# Trepanat_Sensors_3.net
KiCad netlist of a schematic drawn in Altium Designer
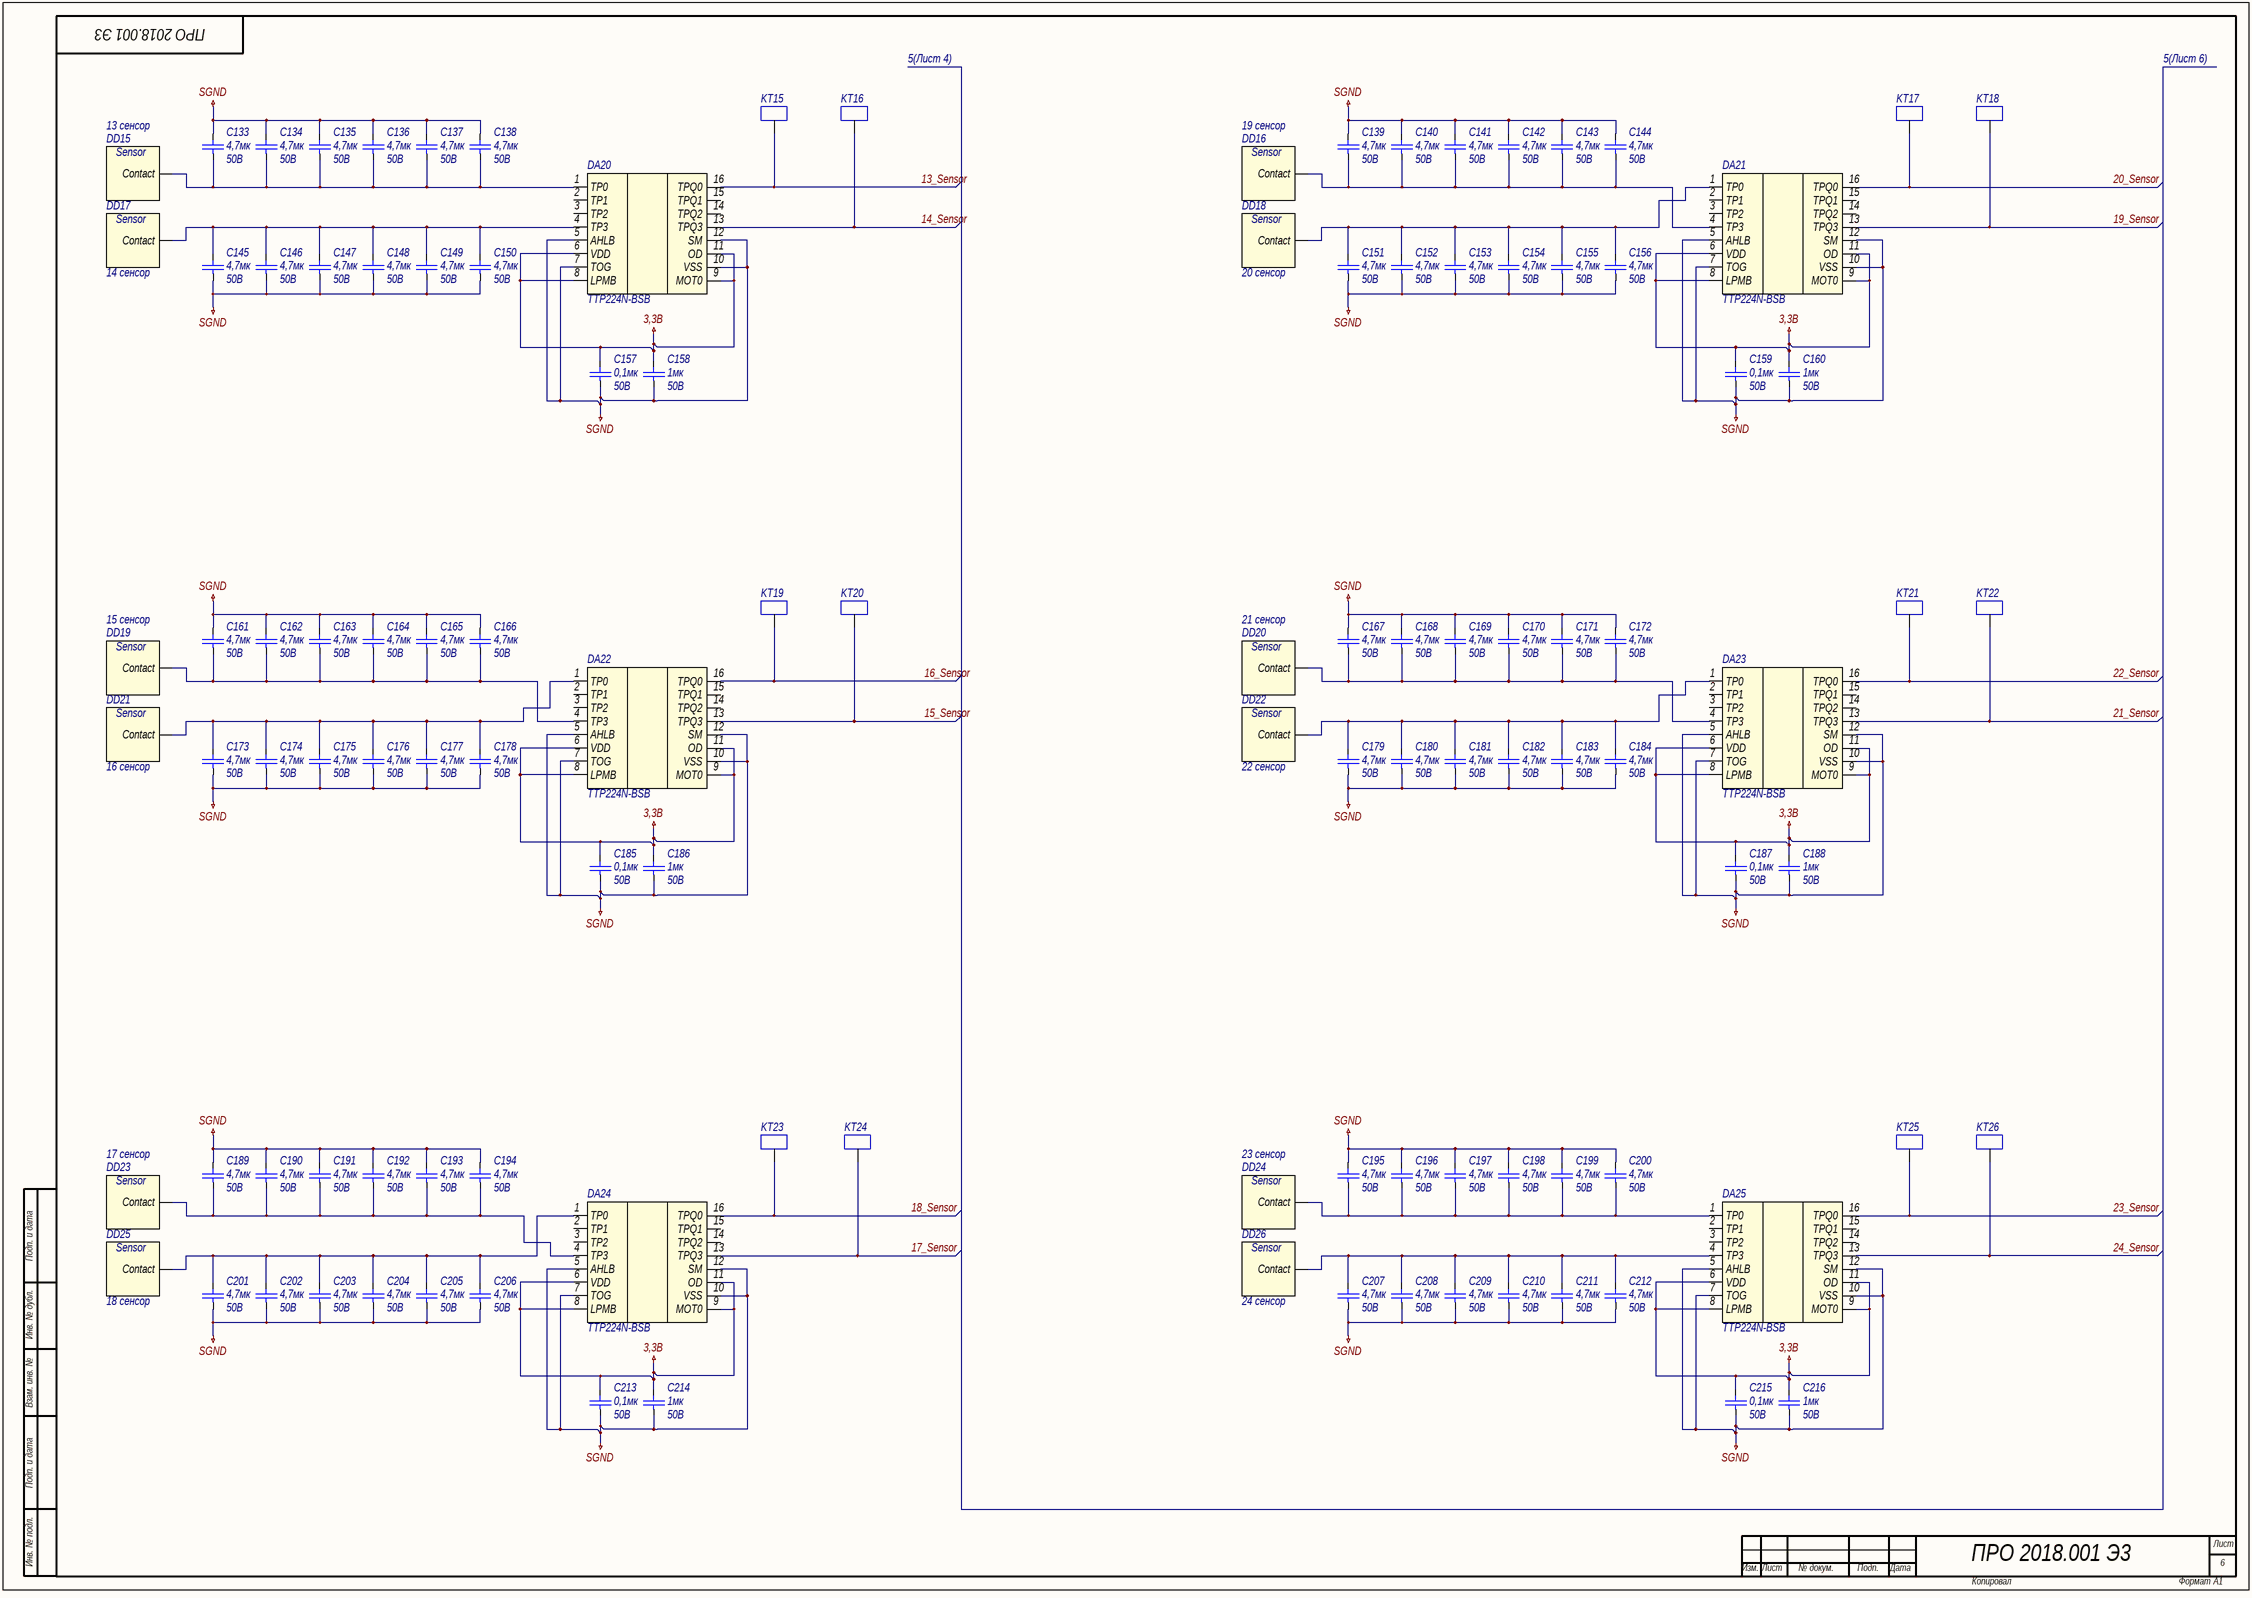
[diagram p0: Trepanat_Sensors_3.SchDoc]

(export (version "E")
  (design (tool "Eeschema 10.0.6"))
  (components
    (comp (ref "C133")
      (value "4,7мк")
      (footprint "ZabugorLib:C0805")
      (description "Конденсатор")
      (fields (field (name "VOLTAGE") "50В"))
      (libsource (lib "ZabugorLib") (part "Capacitor"))
    )
    (comp (ref "C134")
      (value "4,7мк")
      (footprint "ZabugorLib:C0805")
      (description "Конденсатор")
      (fields (field (name "VOLTAGE") "50В"))
      (libsource (lib "ZabugorLib") (part "Capacitor"))
    )
    (comp (ref "C135")
      (value "4,7мк")
      (footprint "ZabugorLib:C0805")
      (description "Конденсатор")
      (fields (field (name "VOLTAGE") "50В"))
      (libsource (lib "ZabugorLib") (part "Capacitor"))
    )
    (comp (ref "C136")
      (value "4,7мк")
      (footprint "ZabugorLib:C0805")
      (description "Конденсатор")
      (fields (field (name "VOLTAGE") "50В"))
      (libsource (lib "ZabugorLib") (part "Capacitor"))
    )
    (comp (ref "C137")
      (value "4,7мк")
      (footprint "ZabugorLib:C0805")
      (description "Конденсатор")
      (fields (field (name "VOLTAGE") "50В"))
      (libsource (lib "ZabugorLib") (part "Capacitor"))
    )
    (comp (ref "C138")
      (value "4,7мк")
      (footprint "ZabugorLib:C0805")
      (description "Конденсатор")
      (fields (field (name "VOLTAGE") "50В"))
      (libsource (lib "ZabugorLib") (part "Capacitor"))
    )
    (comp (ref "C139")
      (value "4,7мк")
      (footprint "ZabugorLib:C0805")
      (description "Конденсатор")
      (fields (field (name "VOLTAGE") "50В"))
      (libsource (lib "ZabugorLib") (part "Capacitor"))
    )
    (comp (ref "C140")
      (value "4,7мк")
      (footprint "ZabugorLib:C0805")
      (description "Конденсатор")
      (fields (field (name "VOLTAGE") "50В"))
      (libsource (lib "ZabugorLib") (part "Capacitor"))
    )
    (comp (ref "C141")
      (value "4,7мк")
      (footprint "ZabugorLib:C0805")
      (description "Конденсатор")
      (fields (field (name "VOLTAGE") "50В"))
      (libsource (lib "ZabugorLib") (part "Capacitor"))
    )
    (comp (ref "C142")
      (value "4,7мк")
      (footprint "ZabugorLib:C0805")
      (description "Конденсатор")
      (fields (field (name "VOLTAGE") "50В"))
      (libsource (lib "ZabugorLib") (part "Capacitor"))
    )
    (comp (ref "C143")
      (value "4,7мк")
      (footprint "ZabugorLib:C0805")
      (description "Конденсатор")
      (fields (field (name "VOLTAGE") "50В"))
      (libsource (lib "ZabugorLib") (part "Capacitor"))
    )
    (comp (ref "C144")
      (value "4,7мк")
      (footprint "ZabugorLib:C0805")
      (description "Конденсатор")
      (fields (field (name "VOLTAGE") "50В"))
      (libsource (lib "ZabugorLib") (part "Capacitor"))
    )
    (comp (ref "C145")
      (value "4,7мк")
      (footprint "ZabugorLib:C0805")
      (description "Конденсатор")
      (fields (field (name "VOLTAGE") "50В"))
      (libsource (lib "ZabugorLib") (part "Capacitor"))
    )
    (comp (ref "C146")
      (value "4,7мк")
      (footprint "ZabugorLib:C0805")
      (description "Конденсатор")
      (fields (field (name "VOLTAGE") "50В"))
      (libsource (lib "ZabugorLib") (part "Capacitor"))
    )
    (comp (ref "C147")
      (value "4,7мк")
      (footprint "ZabugorLib:C0805")
      (description "Конденсатор")
      (fields (field (name "VOLTAGE") "50В"))
      (libsource (lib "ZabugorLib") (part "Capacitor"))
    )
    (comp (ref "C148")
      (value "4,7мк")
      (footprint "ZabugorLib:C0805")
      (description "Конденсатор")
      (fields (field (name "VOLTAGE") "50В"))
      (libsource (lib "ZabugorLib") (part "Capacitor"))
    )
    (comp (ref "C149")
      (value "4,7мк")
      (footprint "ZabugorLib:C0805")
      (description "Конденсатор")
      (fields (field (name "VOLTAGE") "50В"))
      (libsource (lib "ZabugorLib") (part "Capacitor"))
    )
    (comp (ref "C150")
      (value "4,7мк")
      (footprint "ZabugorLib:C0805")
      (description "Конденсатор")
      (fields (field (name "VOLTAGE") "50В"))
      (libsource (lib "ZabugorLib") (part "Capacitor"))
    )
    (comp (ref "C151")
      (value "4,7мк")
      (footprint "ZabugorLib:C0805")
      (description "Конденсатор")
      (fields (field (name "VOLTAGE") "50В"))
      (libsource (lib "ZabugorLib") (part "Capacitor"))
    )
    (comp (ref "C152")
      (value "4,7мк")
      (footprint "ZabugorLib:C0805")
      (description "Конденсатор")
      (fields (field (name "VOLTAGE") "50В"))
      (libsource (lib "ZabugorLib") (part "Capacitor"))
    )
    (comp (ref "C153")
      (value "4,7мк")
      (footprint "ZabugorLib:C0805")
      (description "Конденсатор")
      (fields (field (name "VOLTAGE") "50В"))
      (libsource (lib "ZabugorLib") (part "Capacitor"))
    )
    (comp (ref "C154")
      (value "4,7мк")
      (footprint "ZabugorLib:C0805")
      (description "Конденсатор")
      (fields (field (name "VOLTAGE") "50В"))
      (libsource (lib "ZabugorLib") (part "Capacitor"))
    )
    (comp (ref "C155")
      (value "4,7мк")
      (footprint "ZabugorLib:C0805")
      (description "Конденсатор")
      (fields (field (name "VOLTAGE") "50В"))
      (libsource (lib "ZabugorLib") (part "Capacitor"))
    )
    (comp (ref "C156")
      (value "4,7мк")
      (footprint "ZabugorLib:C0805")
      (description "Конденсатор")
      (fields (field (name "VOLTAGE") "50В"))
      (libsource (lib "ZabugorLib") (part "Capacitor"))
    )
    (comp (ref "C157")
      (value "0,1мк")
      (footprint "ZabugorLib:C0805")
      (description "Конденсатор")
      (fields (field (name "VOLTAGE") "50В"))
      (libsource (lib "ZabugorLib") (part "Capacitor"))
    )
    (comp (ref "C158")
      (value "1мк")
      (footprint "ZabugorLib:C0805")
      (description "Конденсатор")
      (fields (field (name "VOLTAGE") "50В"))
      (libsource (lib "ZabugorLib") (part "Capacitor"))
    )
    (comp (ref "C159")
      (value "0,1мк")
      (footprint "ZabugorLib:C0805")
      (description "Конденсатор")
      (fields (field (name "VOLTAGE") "50В"))
      (libsource (lib "ZabugorLib") (part "Capacitor"))
    )
    (comp (ref "C160")
      (value "1мк")
      (footprint "ZabugorLib:C0805")
      (description "Конденсатор")
      (fields (field (name "VOLTAGE") "50В"))
      (libsource (lib "ZabugorLib") (part "Capacitor"))
    )
    (comp (ref "C161")
      (value "4,7мк")
      (footprint "ZabugorLib:C0805")
      (description "Конденсатор")
      (fields (field (name "VOLTAGE") "50В"))
      (libsource (lib "ZabugorLib") (part "Capacitor"))
    )
    (comp (ref "C162")
      (value "4,7мк")
      (footprint "ZabugorLib:C0805")
      (description "Конденсатор")
      (fields (field (name "VOLTAGE") "50В"))
      (libsource (lib "ZabugorLib") (part "Capacitor"))
    )
    (comp (ref "C163")
      (value "4,7мк")
      (footprint "ZabugorLib:C0805")
      (description "Конденсатор")
      (fields (field (name "VOLTAGE") "50В"))
      (libsource (lib "ZabugorLib") (part "Capacitor"))
    )
    (comp (ref "C164")
      (value "4,7мк")
      (footprint "ZabugorLib:C0805")
      (description "Конденсатор")
      (fields (field (name "VOLTAGE") "50В"))
      (libsource (lib "ZabugorLib") (part "Capacitor"))
    )
    (comp (ref "C165")
      (value "4,7мк")
      (footprint "ZabugorLib:C0805")
      (description "Конденсатор")
      (fields (field (name "VOLTAGE") "50В"))
      (libsource (lib "ZabugorLib") (part "Capacitor"))
    )
    (comp (ref "C166")
      (value "4,7мк")
      (footprint "ZabugorLib:C0805")
      (description "Конденсатор")
      (fields (field (name "VOLTAGE") "50В"))
      (libsource (lib "ZabugorLib") (part "Capacitor"))
    )
    (comp (ref "C167")
      (value "4,7мк")
      (footprint "ZabugorLib:C0805")
      (description "Конденсатор")
      (fields (field (name "VOLTAGE") "50В"))
      (libsource (lib "ZabugorLib") (part "Capacitor"))
    )
    (comp (ref "C168")
      (value "4,7мк")
      (footprint "ZabugorLib:C0805")
      (description "Конденсатор")
      (fields (field (name "VOLTAGE") "50В"))
      (libsource (lib "ZabugorLib") (part "Capacitor"))
    )
    (comp (ref "C169")
      (value "4,7мк")
      (footprint "ZabugorLib:C0805")
      (description "Конденсатор")
      (fields (field (name "VOLTAGE") "50В"))
      (libsource (lib "ZabugorLib") (part "Capacitor"))
    )
    (comp (ref "C170")
      (value "4,7мк")
      (footprint "ZabugorLib:C0805")
      (description "Конденсатор")
      (fields (field (name "VOLTAGE") "50В"))
      (libsource (lib "ZabugorLib") (part "Capacitor"))
    )
    (comp (ref "C171")
      (value "4,7мк")
      (footprint "ZabugorLib:C0805")
      (description "Конденсатор")
      (fields (field (name "VOLTAGE") "50В"))
      (libsource (lib "ZabugorLib") (part "Capacitor"))
    )
    (comp (ref "C172")
      (value "4,7мк")
      (footprint "ZabugorLib:C0805")
      (description "Конденсатор")
      (fields (field (name "VOLTAGE") "50В"))
      (libsource (lib "ZabugorLib") (part "Capacitor"))
    )
    (comp (ref "C173")
      (value "4,7мк")
      (footprint "ZabugorLib:C0805")
      (description "Конденсатор")
      (fields (field (name "VOLTAGE") "50В"))
      (libsource (lib "ZabugorLib") (part "Capacitor"))
    )
    (comp (ref "C174")
      (value "4,7мк")
      (footprint "ZabugorLib:C0805")
      (description "Конденсатор")
      (fields (field (name "VOLTAGE") "50В"))
      (libsource (lib "ZabugorLib") (part "Capacitor"))
    )
    (comp (ref "C175")
      (value "4,7мк")
      (footprint "ZabugorLib:C0805")
      (description "Конденсатор")
      (fields (field (name "VOLTAGE") "50В"))
      (libsource (lib "ZabugorLib") (part "Capacitor"))
    )
    (comp (ref "C176")
      (value "4,7мк")
      (footprint "ZabugorLib:C0805")
      (description "Конденсатор")
      (fields (field (name "VOLTAGE") "50В"))
      (libsource (lib "ZabugorLib") (part "Capacitor"))
    )
    (comp (ref "C177")
      (value "4,7мк")
      (footprint "ZabugorLib:C0805")
      (description "Конденсатор")
      (fields (field (name "VOLTAGE") "50В"))
      (libsource (lib "ZabugorLib") (part "Capacitor"))
    )
    (comp (ref "C178")
      (value "4,7мк")
      (footprint "ZabugorLib:C0805")
      (description "Конденсатор")
      (fields (field (name "VOLTAGE") "50В"))
      (libsource (lib "ZabugorLib") (part "Capacitor"))
    )
    (comp (ref "C179")
      (value "4,7мк")
      (footprint "ZabugorLib:C0805")
      (description "Конденсатор")
      (fields (field (name "VOLTAGE") "50В"))
      (libsource (lib "ZabugorLib") (part "Capacitor"))
    )
    (comp (ref "C180")
      (value "4,7мк")
      (footprint "ZabugorLib:C0805")
      (description "Конденсатор")
      (fields (field (name "VOLTAGE") "50В"))
      (libsource (lib "ZabugorLib") (part "Capacitor"))
    )
    (comp (ref "C181")
      (value "4,7мк")
      (footprint "ZabugorLib:C0805")
      (description "Конденсатор")
      (fields (field (name "VOLTAGE") "50В"))
      (libsource (lib "ZabugorLib") (part "Capacitor"))
    )
    (comp (ref "C182")
      (value "4,7мк")
      (footprint "ZabugorLib:C0805")
      (description "Конденсатор")
      (fields (field (name "VOLTAGE") "50В"))
      (libsource (lib "ZabugorLib") (part "Capacitor"))
    )
    (comp (ref "C183")
      (value "4,7мк")
      (footprint "ZabugorLib:C0805")
      (description "Конденсатор")
      (fields (field (name "VOLTAGE") "50В"))
      (libsource (lib "ZabugorLib") (part "Capacitor"))
    )
    (comp (ref "C184")
      (value "4,7мк")
      (footprint "ZabugorLib:C0805")
      (description "Конденсатор")
      (fields (field (name "VOLTAGE") "50В"))
      (libsource (lib "ZabugorLib") (part "Capacitor"))
    )
    (comp (ref "C185")
      (value "0,1мк")
      (footprint "ZabugorLib:C0805")
      (description "Конденсатор")
      (fields (field (name "VOLTAGE") "50В"))
      (libsource (lib "ZabugorLib") (part "Capacitor"))
    )
    (comp (ref "C186")
      (value "1мк")
      (footprint "ZabugorLib:C0805")
      (description "Конденсатор")
      (fields (field (name "VOLTAGE") "50В"))
      (libsource (lib "ZabugorLib") (part "Capacitor"))
    )
    (comp (ref "C187")
      (value "0,1мк")
      (footprint "ZabugorLib:C0805")
      (description "Конденсатор")
      (fields (field (name "VOLTAGE") "50В"))
      (libsource (lib "ZabugorLib") (part "Capacitor"))
    )
    (comp (ref "C188")
      (value "1мк")
      (footprint "ZabugorLib:C0805")
      (description "Конденсатор")
      (fields (field (name "VOLTAGE") "50В"))
      (libsource (lib "ZabugorLib") (part "Capacitor"))
    )
    (comp (ref "C189")
      (value "4,7мк")
      (footprint "ZabugorLib:C0805")
      (description "Конденсатор")
      (fields (field (name "VOLTAGE") "50В"))
      (libsource (lib "ZabugorLib") (part "Capacitor"))
    )
    (comp (ref "C190")
      (value "4,7мк")
      (footprint "ZabugorLib:C0805")
      (description "Конденсатор")
      (fields (field (name "VOLTAGE") "50В"))
      (libsource (lib "ZabugorLib") (part "Capacitor"))
    )
    (comp (ref "C191")
      (value "4,7мк")
      (footprint "ZabugorLib:C0805")
      (description "Конденсатор")
      (fields (field (name "VOLTAGE") "50В"))
      (libsource (lib "ZabugorLib") (part "Capacitor"))
    )
    (comp (ref "C192")
      (value "4,7мк")
      (footprint "ZabugorLib:C0805")
      (description "Конденсатор")
      (fields (field (name "VOLTAGE") "50В"))
      (libsource (lib "ZabugorLib") (part "Capacitor"))
    )
    (comp (ref "C193")
      (value "4,7мк")
      (footprint "ZabugorLib:C0805")
      (description "Конденсатор")
      (fields (field (name "VOLTAGE") "50В"))
      (libsource (lib "ZabugorLib") (part "Capacitor"))
    )
    (comp (ref "C194")
      (value "4,7мк")
      (footprint "ZabugorLib:C0805")
      (description "Конденсатор")
      (fields (field (name "VOLTAGE") "50В"))
      (libsource (lib "ZabugorLib") (part "Capacitor"))
    )
    (comp (ref "C195")
      (value "4,7мк")
      (footprint "ZabugorLib:C0805")
      (description "Конденсатор")
      (fields (field (name "VOLTAGE") "50В"))
      (libsource (lib "ZabugorLib") (part "Capacitor"))
    )
    (comp (ref "C196")
      (value "4,7мк")
      (footprint "ZabugorLib:C0805")
      (description "Конденсатор")
      (fields (field (name "VOLTAGE") "50В"))
      (libsource (lib "ZabugorLib") (part "Capacitor"))
    )
    (comp (ref "C197")
      (value "4,7мк")
      (footprint "ZabugorLib:C0805")
      (description "Конденсатор")
      (fields (field (name "VOLTAGE") "50В"))
      (libsource (lib "ZabugorLib") (part "Capacitor"))
    )
    (comp (ref "C198")
      (value "4,7мк")
      (footprint "ZabugorLib:C0805")
      (description "Конденсатор")
      (fields (field (name "VOLTAGE") "50В"))
      (libsource (lib "ZabugorLib") (part "Capacitor"))
    )
    (comp (ref "C199")
      (value "4,7мк")
      (footprint "ZabugorLib:C0805")
      (description "Конденсатор")
      (fields (field (name "VOLTAGE") "50В"))
      (libsource (lib "ZabugorLib") (part "Capacitor"))
    )
    (comp (ref "C200")
      (value "4,7мк")
      (footprint "ZabugorLib:C0805")
      (description "Конденсатор")
      (fields (field (name "VOLTAGE") "50В"))
      (libsource (lib "ZabugorLib") (part "Capacitor"))
    )
    (comp (ref "C201")
      (value "4,7мк")
      (footprint "ZabugorLib:C0805")
      (description "Конденсатор")
      (fields (field (name "VOLTAGE") "50В"))
      (libsource (lib "ZabugorLib") (part "Capacitor"))
    )
    (comp (ref "C202")
      (value "4,7мк")
      (footprint "ZabugorLib:C0805")
      (description "Конденсатор")
      (fields (field (name "VOLTAGE") "50В"))
      (libsource (lib "ZabugorLib") (part "Capacitor"))
    )
    (comp (ref "C203")
      (value "4,7мк")
      (footprint "ZabugorLib:C0805")
      (description "Конденсатор")
      (fields (field (name "VOLTAGE") "50В"))
      (libsource (lib "ZabugorLib") (part "Capacitor"))
    )
    (comp (ref "C204")
      (value "4,7мк")
      (footprint "ZabugorLib:C0805")
      (description "Конденсатор")
      (fields (field (name "VOLTAGE") "50В"))
      (libsource (lib "ZabugorLib") (part "Capacitor"))
    )
    (comp (ref "C205")
      (value "4,7мк")
      (footprint "ZabugorLib:C0805")
      (description "Конденсатор")
      (fields (field (name "VOLTAGE") "50В"))
      (libsource (lib "ZabugorLib") (part "Capacitor"))
    )
    (comp (ref "C206")
      (value "4,7мк")
      (footprint "ZabugorLib:C0805")
      (description "Конденсатор")
      (fields (field (name "VOLTAGE") "50В"))
      (libsource (lib "ZabugorLib") (part "Capacitor"))
    )
    (comp (ref "C207")
      (value "4,7мк")
      (footprint "ZabugorLib:C0805")
      (description "Конденсатор")
      (fields (field (name "VOLTAGE") "50В"))
      (libsource (lib "ZabugorLib") (part "Capacitor"))
    )
    (comp (ref "C208")
      (value "4,7мк")
      (footprint "ZabugorLib:C0805")
      (description "Конденсатор")
      (fields (field (name "VOLTAGE") "50В"))
      (libsource (lib "ZabugorLib") (part "Capacitor"))
    )
    (comp (ref "C209")
      (value "4,7мк")
      (footprint "ZabugorLib:C0805")
      (description "Конденсатор")
      (fields (field (name "VOLTAGE") "50В"))
      (libsource (lib "ZabugorLib") (part "Capacitor"))
    )
    (comp (ref "C210")
      (value "4,7мк")
      (footprint "ZabugorLib:C0805")
      (description "Конденсатор")
      (fields (field (name "VOLTAGE") "50В"))
      (libsource (lib "ZabugorLib") (part "Capacitor"))
    )
    (comp (ref "C211")
      (value "4,7мк")
      (footprint "ZabugorLib:C0805")
      (description "Конденсатор")
      (fields (field (name "VOLTAGE") "50В"))
      (libsource (lib "ZabugorLib") (part "Capacitor"))
    )
    (comp (ref "C212")
      (value "4,7мк")
      (footprint "ZabugorLib:C0805")
      (description "Конденсатор")
      (fields (field (name "VOLTAGE") "50В"))
      (libsource (lib "ZabugorLib") (part "Capacitor"))
    )
    (comp (ref "C213")
      (value "0,1мк")
      (footprint "ZabugorLib:C0805")
      (description "Конденсатор")
      (fields (field (name "VOLTAGE") "50В"))
      (libsource (lib "ZabugorLib") (part "Capacitor"))
    )
    (comp (ref "C214")
      (value "1мк")
      (footprint "ZabugorLib:C0805")
      (description "Конденсатор")
      (fields (field (name "VOLTAGE") "50В"))
      (libsource (lib "ZabugorLib") (part "Capacitor"))
    )
    (comp (ref "C215")
      (value "0,1мк")
      (footprint "ZabugorLib:C0805")
      (description "Конденсатор")
      (fields (field (name "VOLTAGE") "50В"))
      (libsource (lib "ZabugorLib") (part "Capacitor"))
    )
    (comp (ref "C216")
      (value "1мк")
      (footprint "ZabugorLib:C0805")
      (description "Конденсатор")
      (fields (field (name "VOLTAGE") "50В"))
      (libsource (lib "ZabugorLib") (part "Capacitor"))
    )
    (comp (ref "DA20")
      (value "TTP224N-BSB")
      (footprint "ZabugorLib:SSOP16")
      (description "4 keys Touch Pad Detector IC")
      (libsource (lib "ZabugorLib") (part "TTP224N-BSB"))
    )
    (comp (ref "DA21")
      (value "TTP224N-BSB")
      (footprint "ZabugorLib:SSOP16")
      (description "4 keys Touch Pad Detector IC")
      (libsource (lib "ZabugorLib") (part "TTP224N-BSB"))
    )
    (comp (ref "DA22")
      (value "TTP224N-BSB")
      (footprint "ZabugorLib:SSOP16")
      (description "4 keys Touch Pad Detector IC")
      (libsource (lib "ZabugorLib") (part "TTP224N-BSB"))
    )
    (comp (ref "DA23")
      (value "TTP224N-BSB")
      (footprint "ZabugorLib:SSOP16")
      (description "4 keys Touch Pad Detector IC")
      (libsource (lib "ZabugorLib") (part "TTP224N-BSB"))
    )
    (comp (ref "DA24")
      (value "TTP224N-BSB")
      (footprint "ZabugorLib:SSOP16")
      (description "4 keys Touch Pad Detector IC")
      (libsource (lib "ZabugorLib") (part "TTP224N-BSB"))
    )
    (comp (ref "DA25")
      (value "TTP224N-BSB")
      (footprint "ZabugorLib:SSOP16")
      (description "4 keys Touch Pad Detector IC")
      (libsource (lib "ZabugorLib") (part "TTP224N-BSB"))
    )
    (comp (ref "DD15")
      (value "13 сенсор")
      (footprint "ZabugorLib:SENSOR")
      (description "Сенсорная площадка")
      (libsource (lib "ZabugorLib") (part "Sensor"))
    )
    (comp (ref "DD16")
      (value "19 сенсор")
      (footprint "ZabugorLib:SENSOR")
      (description "Сенсорная площадка")
      (libsource (lib "ZabugorLib") (part "Sensor"))
    )
    (comp (ref "DD17")
      (value "14 сенсор")
      (footprint "ZabugorLib:SENSOR")
      (description "Сенсорная площадка")
      (libsource (lib "ZabugorLib") (part "Sensor"))
    )
    (comp (ref "DD18")
      (value "20 сенсор")
      (footprint "ZabugorLib:SENSOR")
      (description "Сенсорная площадка")
      (libsource (lib "ZabugorLib") (part "Sensor"))
    )
    (comp (ref "DD19")
      (value "15 сенсор")
      (footprint "ZabugorLib:SENSOR")
      (description "Сенсорная площадка")
      (libsource (lib "ZabugorLib") (part "Sensor"))
    )
    (comp (ref "DD20")
      (value "21 сенсор")
      (footprint "ZabugorLib:SENSOR")
      (description "Сенсорная площадка")
      (libsource (lib "ZabugorLib") (part "Sensor"))
    )
    (comp (ref "DD21")
      (value "16 сенсор")
      (footprint "ZabugorLib:SENSOR")
      (description "Сенсорная площадка")
      (libsource (lib "ZabugorLib") (part "Sensor"))
    )
    (comp (ref "DD22")
      (value "22 сенсор")
      (footprint "ZabugorLib:SENSOR")
      (description "Сенсорная площадка")
      (libsource (lib "ZabugorLib") (part "Sensor"))
    )
    (comp (ref "DD23")
      (value "17 сенсор")
      (footprint "ZabugorLib:SENSOR")
      (description "Сенсорная площадка")
      (libsource (lib "ZabugorLib") (part "Sensor"))
    )
    (comp (ref "DD24")
      (value "23 сенсор")
      (footprint "ZabugorLib:SENSOR")
      (description "Сенсорная площадка")
      (libsource (lib "ZabugorLib") (part "Sensor"))
    )
    (comp (ref "DD25")
      (value "18 сенсор")
      (footprint "ZabugorLib:SENSOR")
      (description "Сенсорная площадка")
      (libsource (lib "ZabugorLib") (part "Sensor"))
    )
    (comp (ref "DD26")
      (value "24 сенсор")
      (footprint "ZabugorLib:SENSOR")
      (description "Сенсорная площадка")
      (libsource (lib "ZabugorLib") (part "Sensor"))
    )
    (comp (ref "KT15")
      (value "KT")
      (footprint "ZabugorLib:КТ")
      (description "Контрольная точка")
      (libsource (lib "ZabugorLib") (part "KT"))
    )
    (comp (ref "KT16")
      (value "KT")
      (footprint "ZabugorLib:КТ")
      (description "Контрольная точка")
      (libsource (lib "ZabugorLib") (part "KT"))
    )
    (comp (ref "KT17")
      (value "KT")
      (footprint "ZabugorLib:КТ")
      (description "Контрольная точка")
      (libsource (lib "ZabugorLib") (part "KT"))
    )
    (comp (ref "KT18")
      (value "KT")
      (footprint "ZabugorLib:КТ")
      (description "Контрольная точка")
      (libsource (lib "ZabugorLib") (part "KT"))
    )
    (comp (ref "KT19")
      (value "KT")
      (footprint "ZabugorLib:КТ")
      (description "Контрольная точка")
      (libsource (lib "ZabugorLib") (part "KT"))
    )
    (comp (ref "KT20")
      (value "KT")
      (footprint "ZabugorLib:КТ")
      (description "Контрольная точка")
      (libsource (lib "ZabugorLib") (part "KT"))
    )
    (comp (ref "KT21")
      (value "KT")
      (footprint "ZabugorLib:КТ")
      (description "Контрольная точка")
      (libsource (lib "ZabugorLib") (part "KT"))
    )
    (comp (ref "KT22")
      (value "KT")
      (footprint "ZabugorLib:КТ")
      (description "Контрольная точка")
      (libsource (lib "ZabugorLib") (part "KT"))
    )
    (comp (ref "KT23")
      (value "KT")
      (footprint "ZabugorLib:КТ")
      (description "Контрольная точка")
      (libsource (lib "ZabugorLib") (part "KT"))
    )
    (comp (ref "KT24")
      (value "KT")
      (footprint "ZabugorLib:КТ")
      (description "Контрольная точка")
      (libsource (lib "ZabugorLib") (part "KT"))
    )
    (comp (ref "KT25")
      (value "KT")
      (footprint "ZabugorLib:КТ")
      (description "Контрольная точка")
      (libsource (lib "ZabugorLib") (part "KT"))
    )
    (comp (ref "KT26")
      (value "KT")
      (footprint "ZabugorLib:КТ")
      (description "Контрольная точка")
      (libsource (lib "ZabugorLib") (part "KT"))
    )
  )
  (nets
    (net (code "1") (name "/13_Sensor") (class "Default")
      (node (ref "DA20") (pin "16") (pinfunction "TPQ0_16") (pintype "power_in"))
      (node (ref "KT15") (pin "1") (pinfunction "1_1") (pintype "passive"))
    )
    (net (code "2") (name "/14_Sensor") (class "Default")
      (node (ref "DA20") (pin "13") (pinfunction "TPQ3_13") (pintype "power_in"))
      (node (ref "KT16") (pin "1") (pinfunction "1_1") (pintype "passive"))
    )
    (net (code "3") (name "/15_Sensor") (class "Default")
      (node (ref "DA22") (pin "13") (pinfunction "TPQ3_13") (pintype "power_in"))
      (node (ref "KT20") (pin "1") (pinfunction "1_1") (pintype "passive"))
    )
    (net (code "4") (name "/16_Sensor") (class "Default")
      (node (ref "DA22") (pin "16") (pinfunction "TPQ0_16") (pintype "power_in"))
      (node (ref "KT19") (pin "1") (pinfunction "1_1") (pintype "passive"))
    )
    (net (code "5") (name "/17_Sensor") (class "Default")
      (node (ref "DA24") (pin "13") (pinfunction "TPQ3_13") (pintype "power_in"))
      (node (ref "KT24") (pin "1") (pinfunction "1_1") (pintype "passive"))
    )
    (net (code "6") (name "/18_Sensor") (class "Default")
      (node (ref "DA24") (pin "16") (pinfunction "TPQ0_16") (pintype "power_in"))
      (node (ref "KT23") (pin "1") (pinfunction "1_1") (pintype "passive"))
    )
    (net (code "7") (name "/19_Sensor") (class "Default")
      (node (ref "DA21") (pin "13") (pinfunction "TPQ3_13") (pintype "power_in"))
      (node (ref "KT18") (pin "1") (pinfunction "1_1") (pintype "passive"))
    )
    (net (code "8") (name "/20_Sensor") (class "Default")
      (node (ref "DA21") (pin "16") (pinfunction "TPQ0_16") (pintype "power_in"))
      (node (ref "KT17") (pin "1") (pinfunction "1_1") (pintype "passive"))
    )
    (net (code "9") (name "/21_Sensor") (class "Default")
      (node (ref "DA23") (pin "13") (pinfunction "TPQ3_13") (pintype "power_in"))
      (node (ref "KT22") (pin "1") (pinfunction "1_1") (pintype "passive"))
    )
    (net (code "10") (name "/22_Sensor") (class "Default")
      (node (ref "DA23") (pin "16") (pinfunction "TPQ0_16") (pintype "power_in"))
      (node (ref "KT21") (pin "1") (pinfunction "1_1") (pintype "passive"))
    )
    (net (code "11") (name "/23_Sensor") (class "Default")
      (node (ref "DA25") (pin "16") (pinfunction "TPQ0_16") (pintype "power_in"))
      (node (ref "KT25") (pin "1") (pinfunction "1_1") (pintype "passive"))
    )
    (net (code "12") (name "/24_Sensor") (class "Default")
      (node (ref "DA25") (pin "13") (pinfunction "TPQ3_13") (pintype "power_in"))
      (node (ref "KT26") (pin "1") (pinfunction "1_1") (pintype "passive"))
    )
    (net (code "13") (name "3,3B") (class "Default")
      (node (ref "C157") (pin "2") (pinfunction "2_2") (pintype "passive"))
      (node (ref "C158") (pin "2") (pinfunction "2_2") (pintype "passive"))
      (node (ref "C159") (pin "2") (pinfunction "2_2") (pintype "passive"))
      (node (ref "C160") (pin "2") (pinfunction "2_2") (pintype "passive"))
      (node (ref "C185") (pin "2") (pinfunction "2_2") (pintype "passive"))
      (node (ref "C186") (pin "2") (pinfunction "2_2") (pintype "passive"))
      (node (ref "C187") (pin "2") (pinfunction "2_2") (pintype "passive"))
      (node (ref "C188") (pin "2") (pinfunction "2_2") (pintype "passive"))
      (node (ref "C213") (pin "2") (pinfunction "2_2") (pintype "passive"))
      (node (ref "C214") (pin "2") (pinfunction "2_2") (pintype "passive"))
      (node (ref "C215") (pin "2") (pinfunction "2_2") (pintype "passive"))
      (node (ref "C216") (pin "2") (pinfunction "2_2") (pintype "passive"))
      (node (ref "DA20") (pin "11") (pinfunction "OD_11") (pintype "power_in"))
      (node (ref "DA20") (pin "6") (pinfunction "VDD_6") (pintype "power_in"))
      (node (ref "DA20") (pin "8") (pinfunction "LPMB_8") (pintype "power_in"))
      (node (ref "DA20") (pin "9") (pinfunction "MOT0_9") (pintype "power_in"))
      (node (ref "DA21") (pin "11") (pinfunction "OD_11") (pintype "power_in"))
      (node (ref "DA21") (pin "6") (pinfunction "VDD_6") (pintype "power_in"))
      (node (ref "DA21") (pin "8") (pinfunction "LPMB_8") (pintype "power_in"))
      (node (ref "DA21") (pin "9") (pinfunction "MOT0_9") (pintype "power_in"))
      (node (ref "DA22") (pin "11") (pinfunction "OD_11") (pintype "power_in"))
      (node (ref "DA22") (pin "6") (pinfunction "VDD_6") (pintype "power_in"))
      (node (ref "DA22") (pin "8") (pinfunction "LPMB_8") (pintype "power_in"))
      (node (ref "DA22") (pin "9") (pinfunction "MOT0_9") (pintype "power_in"))
      (node (ref "DA23") (pin "11") (pinfunction "OD_11") (pintype "power_in"))
      (node (ref "DA23") (pin "6") (pinfunction "VDD_6") (pintype "power_in"))
      (node (ref "DA23") (pin "8") (pinfunction "LPMB_8") (pintype "power_in"))
      (node (ref "DA23") (pin "9") (pinfunction "MOT0_9") (pintype "power_in"))
      (node (ref "DA24") (pin "11") (pinfunction "OD_11") (pintype "power_in"))
      (node (ref "DA24") (pin "6") (pinfunction "VDD_6") (pintype "power_in"))
      (node (ref "DA24") (pin "8") (pinfunction "LPMB_8") (pintype "power_in"))
      (node (ref "DA24") (pin "9") (pinfunction "MOT0_9") (pintype "power_in"))
      (node (ref "DA25") (pin "11") (pinfunction "OD_11") (pintype "power_in"))
      (node (ref "DA25") (pin "6") (pinfunction "VDD_6") (pintype "power_in"))
      (node (ref "DA25") (pin "8") (pinfunction "LPMB_8") (pintype "power_in"))
      (node (ref "DA25") (pin "9") (pinfunction "MOT0_9") (pintype "power_in"))
    )
    (net (code "14") (name "Net-(DA20-TP0)") (class "Default")
      (node (ref "C133") (pin "1") (pinfunction "1_1") (pintype "passive"))
      (node (ref "C134") (pin "1") (pinfunction "1_1") (pintype "passive"))
      (node (ref "C135") (pin "1") (pinfunction "1_1") (pintype "passive"))
      (node (ref "C136") (pin "1") (pinfunction "1_1") (pintype "passive"))
      (node (ref "C137") (pin "1") (pinfunction "1_1") (pintype "passive"))
      (node (ref "C138") (pin "1") (pinfunction "1_1") (pintype "passive"))
      (node (ref "DA20") (pin "1") (pinfunction "TP0_1") (pintype "power_in"))
      (node (ref "DD15") (pin "1") (pinfunction "Contact_1") (pintype "power_in"))
    )
    (net (code "15") (name "Net-(DA20-TP3)") (class "Default")
      (node (ref "C145") (pin "2") (pinfunction "2_2") (pintype "passive"))
      (node (ref "C146") (pin "2") (pinfunction "2_2") (pintype "passive"))
      (node (ref "C147") (pin "2") (pinfunction "2_2") (pintype "passive"))
      (node (ref "C148") (pin "2") (pinfunction "2_2") (pintype "passive"))
      (node (ref "C149") (pin "2") (pinfunction "2_2") (pintype "passive"))
      (node (ref "C150") (pin "2") (pinfunction "2_2") (pintype "passive"))
      (node (ref "DA20") (pin "4") (pinfunction "TP3_4") (pintype "power_in"))
      (node (ref "DD17") (pin "1") (pinfunction "Contact_1") (pintype "power_in"))
    )
    (net (code "16") (name "Net-(DA21-TP0)") (class "Default")
      (node (ref "C151") (pin "2") (pinfunction "2_2") (pintype "passive"))
      (node (ref "C152") (pin "2") (pinfunction "2_2") (pintype "passive"))
      (node (ref "C153") (pin "2") (pinfunction "2_2") (pintype "passive"))
      (node (ref "C154") (pin "2") (pinfunction "2_2") (pintype "passive"))
      (node (ref "C155") (pin "2") (pinfunction "2_2") (pintype "passive"))
      (node (ref "C156") (pin "2") (pinfunction "2_2") (pintype "passive"))
      (node (ref "DA21") (pin "1") (pinfunction "TP0_1") (pintype "power_in"))
      (node (ref "DD18") (pin "1") (pinfunction "Contact_1") (pintype "power_in"))
    )
    (net (code "17") (name "Net-(DA21-TP3)") (class "Default")
      (node (ref "C139") (pin "1") (pinfunction "1_1") (pintype "passive"))
      (node (ref "C140") (pin "1") (pinfunction "1_1") (pintype "passive"))
      (node (ref "C141") (pin "1") (pinfunction "1_1") (pintype "passive"))
      (node (ref "C142") (pin "1") (pinfunction "1_1") (pintype "passive"))
      (node (ref "C143") (pin "1") (pinfunction "1_1") (pintype "passive"))
      (node (ref "C144") (pin "1") (pinfunction "1_1") (pintype "passive"))
      (node (ref "DA21") (pin "4") (pinfunction "TP3_4") (pintype "power_in"))
      (node (ref "DD16") (pin "1") (pinfunction "Contact_1") (pintype "power_in"))
    )
    (net (code "18") (name "Net-(DA22-TP0)") (class "Default")
      (node (ref "C173") (pin "2") (pinfunction "2_2") (pintype "passive"))
      (node (ref "C174") (pin "2") (pinfunction "2_2") (pintype "passive"))
      (node (ref "C175") (pin "2") (pinfunction "2_2") (pintype "passive"))
      (node (ref "C176") (pin "2") (pinfunction "2_2") (pintype "passive"))
      (node (ref "C177") (pin "2") (pinfunction "2_2") (pintype "passive"))
      (node (ref "C178") (pin "2") (pinfunction "2_2") (pintype "passive"))
      (node (ref "DA22") (pin "1") (pinfunction "TP0_1") (pintype "power_in"))
      (node (ref "DD21") (pin "1") (pinfunction "Contact_1") (pintype "power_in"))
    )
    (net (code "19") (name "Net-(DA22-TP3)") (class "Default")
      (node (ref "C161") (pin "1") (pinfunction "1_1") (pintype "passive"))
      (node (ref "C162") (pin "1") (pinfunction "1_1") (pintype "passive"))
      (node (ref "C163") (pin "1") (pinfunction "1_1") (pintype "passive"))
      (node (ref "C164") (pin "1") (pinfunction "1_1") (pintype "passive"))
      (node (ref "C165") (pin "1") (pinfunction "1_1") (pintype "passive"))
      (node (ref "C166") (pin "1") (pinfunction "1_1") (pintype "passive"))
      (node (ref "DA22") (pin "4") (pinfunction "TP3_4") (pintype "power_in"))
      (node (ref "DD19") (pin "1") (pinfunction "Contact_1") (pintype "power_in"))
    )
    (net (code "20") (name "Net-(DA23-TP0)") (class "Default")
      (node (ref "C179") (pin "2") (pinfunction "2_2") (pintype "passive"))
      (node (ref "C180") (pin "2") (pinfunction "2_2") (pintype "passive"))
      (node (ref "C181") (pin "2") (pinfunction "2_2") (pintype "passive"))
      (node (ref "C182") (pin "2") (pinfunction "2_2") (pintype "passive"))
      (node (ref "C183") (pin "2") (pinfunction "2_2") (pintype "passive"))
      (node (ref "C184") (pin "2") (pinfunction "2_2") (pintype "passive"))
      (node (ref "DA23") (pin "1") (pinfunction "TP0_1") (pintype "power_in"))
      (node (ref "DD22") (pin "1") (pinfunction "Contact_1") (pintype "power_in"))
    )
    (net (code "21") (name "Net-(DA23-TP3)") (class "Default")
      (node (ref "C167") (pin "1") (pinfunction "1_1") (pintype "passive"))
      (node (ref "C168") (pin "1") (pinfunction "1_1") (pintype "passive"))
      (node (ref "C169") (pin "1") (pinfunction "1_1") (pintype "passive"))
      (node (ref "C170") (pin "1") (pinfunction "1_1") (pintype "passive"))
      (node (ref "C171") (pin "1") (pinfunction "1_1") (pintype "passive"))
      (node (ref "C172") (pin "1") (pinfunction "1_1") (pintype "passive"))
      (node (ref "DA23") (pin "4") (pinfunction "TP3_4") (pintype "power_in"))
      (node (ref "DD20") (pin "1") (pinfunction "Contact_1") (pintype "power_in"))
    )
    (net (code "22") (name "Net-(DA24-TP0)") (class "Default")
      (node (ref "C201") (pin "2") (pinfunction "2_2") (pintype "passive"))
      (node (ref "C202") (pin "2") (pinfunction "2_2") (pintype "passive"))
      (node (ref "C203") (pin "2") (pinfunction "2_2") (pintype "passive"))
      (node (ref "C204") (pin "2") (pinfunction "2_2") (pintype "passive"))
      (node (ref "C205") (pin "2") (pinfunction "2_2") (pintype "passive"))
      (node (ref "C206") (pin "2") (pinfunction "2_2") (pintype "passive"))
      (node (ref "DA24") (pin "1") (pinfunction "TP0_1") (pintype "power_in"))
      (node (ref "DD25") (pin "1") (pinfunction "Contact_1") (pintype "power_in"))
    )
    (net (code "23") (name "Net-(DA24-TP3)") (class "Default")
      (node (ref "C189") (pin "1") (pinfunction "1_1") (pintype "passive"))
      (node (ref "C190") (pin "1") (pinfunction "1_1") (pintype "passive"))
      (node (ref "C191") (pin "1") (pinfunction "1_1") (pintype "passive"))
      (node (ref "C192") (pin "1") (pinfunction "1_1") (pintype "passive"))
      (node (ref "C193") (pin "1") (pinfunction "1_1") (pintype "passive"))
      (node (ref "C194") (pin "1") (pinfunction "1_1") (pintype "passive"))
      (node (ref "DA24") (pin "4") (pinfunction "TP3_4") (pintype "power_in"))
      (node (ref "DD23") (pin "1") (pinfunction "Contact_1") (pintype "power_in"))
    )
    (net (code "24") (name "Net-(DA25-TP0)") (class "Default")
      (node (ref "C195") (pin "1") (pinfunction "1_1") (pintype "passive"))
      (node (ref "C196") (pin "1") (pinfunction "1_1") (pintype "passive"))
      (node (ref "C197") (pin "1") (pinfunction "1_1") (pintype "passive"))
      (node (ref "C198") (pin "1") (pinfunction "1_1") (pintype "passive"))
      (node (ref "C199") (pin "1") (pinfunction "1_1") (pintype "passive"))
      (node (ref "C200") (pin "1") (pinfunction "1_1") (pintype "passive"))
      (node (ref "DA25") (pin "1") (pinfunction "TP0_1") (pintype "power_in"))
      (node (ref "DD24") (pin "1") (pinfunction "Contact_1") (pintype "power_in"))
    )
    (net (code "25") (name "Net-(DA25-TP3)") (class "Default")
      (node (ref "C207") (pin "2") (pinfunction "2_2") (pintype "passive"))
      (node (ref "C208") (pin "2") (pinfunction "2_2") (pintype "passive"))
      (node (ref "C209") (pin "2") (pinfunction "2_2") (pintype "passive"))
      (node (ref "C210") (pin "2") (pinfunction "2_2") (pintype "passive"))
      (node (ref "C211") (pin "2") (pinfunction "2_2") (pintype "passive"))
      (node (ref "C212") (pin "2") (pinfunction "2_2") (pintype "passive"))
      (node (ref "DA25") (pin "4") (pinfunction "TP3_4") (pintype "power_in"))
      (node (ref "DD26") (pin "1") (pinfunction "Contact_1") (pintype "power_in"))
    )
    (net (code "26") (name "SGND") (class "Default")
      (node (ref "C133") (pin "2") (pinfunction "2_2") (pintype "passive"))
      (node (ref "C134") (pin "2") (pinfunction "2_2") (pintype "passive"))
      (node (ref "C135") (pin "2") (pinfunction "2_2") (pintype "passive"))
      (node (ref "C136") (pin "2") (pinfunction "2_2") (pintype "passive"))
      (node (ref "C137") (pin "2") (pinfunction "2_2") (pintype "passive"))
      (node (ref "C138") (pin "2") (pinfunction "2_2") (pintype "passive"))
      (node (ref "C139") (pin "2") (pinfunction "2_2") (pintype "passive"))
      (node (ref "C140") (pin "2") (pinfunction "2_2") (pintype "passive"))
      (node (ref "C141") (pin "2") (pinfunction "2_2") (pintype "passive"))
      (node (ref "C142") (pin "2") (pinfunction "2_2") (pintype "passive"))
      (node (ref "C143") (pin "2") (pinfunction "2_2") (pintype "passive"))
      (node (ref "C144") (pin "2") (pinfunction "2_2") (pintype "passive"))
      (node (ref "C145") (pin "1") (pinfunction "1_1") (pintype "passive"))
      (node (ref "C146") (pin "1") (pinfunction "1_1") (pintype "passive"))
      (node (ref "C147") (pin "1") (pinfunction "1_1") (pintype "passive"))
      (node (ref "C148") (pin "1") (pinfunction "1_1") (pintype "passive"))
      (node (ref "C149") (pin "1") (pinfunction "1_1") (pintype "passive"))
      (node (ref "C150") (pin "1") (pinfunction "1_1") (pintype "passive"))
      (node (ref "C151") (pin "1") (pinfunction "1_1") (pintype "passive"))
      (node (ref "C152") (pin "1") (pinfunction "1_1") (pintype "passive"))
      (node (ref "C153") (pin "1") (pinfunction "1_1") (pintype "passive"))
      (node (ref "C154") (pin "1") (pinfunction "1_1") (pintype "passive"))
      (node (ref "C155") (pin "1") (pinfunction "1_1") (pintype "passive"))
      (node (ref "C156") (pin "1") (pinfunction "1_1") (pintype "passive"))
      (node (ref "C157") (pin "1") (pinfunction "1_1") (pintype "passive"))
      (node (ref "C158") (pin "1") (pinfunction "1_1") (pintype "passive"))
      (node (ref "C159") (pin "1") (pinfunction "1_1") (pintype "passive"))
      (node (ref "C160") (pin "1") (pinfunction "1_1") (pintype "passive"))
      (node (ref "C161") (pin "2") (pinfunction "2_2") (pintype "passive"))
      (node (ref "C162") (pin "2") (pinfunction "2_2") (pintype "passive"))
      (node (ref "C163") (pin "2") (pinfunction "2_2") (pintype "passive"))
      (node (ref "C164") (pin "2") (pinfunction "2_2") (pintype "passive"))
      (node (ref "C165") (pin "2") (pinfunction "2_2") (pintype "passive"))
      (node (ref "C166") (pin "2") (pinfunction "2_2") (pintype "passive"))
      (node (ref "C167") (pin "2") (pinfunction "2_2") (pintype "passive"))
      (node (ref "C168") (pin "2") (pinfunction "2_2") (pintype "passive"))
      (node (ref "C169") (pin "2") (pinfunction "2_2") (pintype "passive"))
      (node (ref "C170") (pin "2") (pinfunction "2_2") (pintype "passive"))
      (node (ref "C171") (pin "2") (pinfunction "2_2") (pintype "passive"))
      (node (ref "C172") (pin "2") (pinfunction "2_2") (pintype "passive"))
      (node (ref "C173") (pin "1") (pinfunction "1_1") (pintype "passive"))
      (node (ref "C174") (pin "1") (pinfunction "1_1") (pintype "passive"))
      (node (ref "C175") (pin "1") (pinfunction "1_1") (pintype "passive"))
      (node (ref "C176") (pin "1") (pinfunction "1_1") (pintype "passive"))
      (node (ref "C177") (pin "1") (pinfunction "1_1") (pintype "passive"))
      (node (ref "C178") (pin "1") (pinfunction "1_1") (pintype "passive"))
      (node (ref "C179") (pin "1") (pinfunction "1_1") (pintype "passive"))
      (node (ref "C180") (pin "1") (pinfunction "1_1") (pintype "passive"))
      (node (ref "C181") (pin "1") (pinfunction "1_1") (pintype "passive"))
      (node (ref "C182") (pin "1") (pinfunction "1_1") (pintype "passive"))
      (node (ref "C183") (pin "1") (pinfunction "1_1") (pintype "passive"))
      (node (ref "C184") (pin "1") (pinfunction "1_1") (pintype "passive"))
      (node (ref "C185") (pin "1") (pinfunction "1_1") (pintype "passive"))
      (node (ref "C186") (pin "1") (pinfunction "1_1") (pintype "passive"))
      (node (ref "C187") (pin "1") (pinfunction "1_1") (pintype "passive"))
      (node (ref "C188") (pin "1") (pinfunction "1_1") (pintype "passive"))
      (node (ref "C189") (pin "2") (pinfunction "2_2") (pintype "passive"))
      (node (ref "C190") (pin "2") (pinfunction "2_2") (pintype "passive"))
      (node (ref "C191") (pin "2") (pinfunction "2_2") (pintype "passive"))
      (node (ref "C192") (pin "2") (pinfunction "2_2") (pintype "passive"))
      (node (ref "C193") (pin "2") (pinfunction "2_2") (pintype "passive"))
      (node (ref "C194") (pin "2") (pinfunction "2_2") (pintype "passive"))
      (node (ref "C195") (pin "2") (pinfunction "2_2") (pintype "passive"))
      (node (ref "C196") (pin "2") (pinfunction "2_2") (pintype "passive"))
      (node (ref "C197") (pin "2") (pinfunction "2_2") (pintype "passive"))
      (node (ref "C198") (pin "2") (pinfunction "2_2") (pintype "passive"))
      (node (ref "C199") (pin "2") (pinfunction "2_2") (pintype "passive"))
      (node (ref "C200") (pin "2") (pinfunction "2_2") (pintype "passive"))
      (node (ref "C201") (pin "1") (pinfunction "1_1") (pintype "passive"))
      (node (ref "C202") (pin "1") (pinfunction "1_1") (pintype "passive"))
      (node (ref "C203") (pin "1") (pinfunction "1_1") (pintype "passive"))
      (node (ref "C204") (pin "1") (pinfunction "1_1") (pintype "passive"))
      (node (ref "C205") (pin "1") (pinfunction "1_1") (pintype "passive"))
      (node (ref "C206") (pin "1") (pinfunction "1_1") (pintype "passive"))
      (node (ref "C207") (pin "1") (pinfunction "1_1") (pintype "passive"))
      (node (ref "C208") (pin "1") (pinfunction "1_1") (pintype "passive"))
      (node (ref "C209") (pin "1") (pinfunction "1_1") (pintype "passive"))
      (node (ref "C210") (pin "1") (pinfunction "1_1") (pintype "passive"))
      (node (ref "C211") (pin "1") (pinfunction "1_1") (pintype "passive"))
      (node (ref "C212") (pin "1") (pinfunction "1_1") (pintype "passive"))
      (node (ref "C213") (pin "1") (pinfunction "1_1") (pintype "passive"))
      (node (ref "C214") (pin "1") (pinfunction "1_1") (pintype "passive"))
      (node (ref "C215") (pin "1") (pinfunction "1_1") (pintype "passive"))
      (node (ref "C216") (pin "1") (pinfunction "1_1") (pintype "passive"))
      (node (ref "DA20") (pin "10") (pinfunction "VSS_10") (pintype "power_in"))
      (node (ref "DA20") (pin "12") (pinfunction "SM_12") (pintype "power_in"))
      (node (ref "DA20") (pin "5") (pinfunction "AHLB_5") (pintype "power_in"))
      (node (ref "DA20") (pin "7") (pinfunction "TOG_7") (pintype "power_in"))
      (node (ref "DA21") (pin "10") (pinfunction "VSS_10") (pintype "power_in"))
      (node (ref "DA21") (pin "12") (pinfunction "SM_12") (pintype "power_in"))
      (node (ref "DA21") (pin "5") (pinfunction "AHLB_5") (pintype "power_in"))
      (node (ref "DA21") (pin "7") (pinfunction "TOG_7") (pintype "power_in"))
      (node (ref "DA22") (pin "10") (pinfunction "VSS_10") (pintype "power_in"))
      (node (ref "DA22") (pin "12") (pinfunction "SM_12") (pintype "power_in"))
      (node (ref "DA22") (pin "5") (pinfunction "AHLB_5") (pintype "power_in"))
      (node (ref "DA22") (pin "7") (pinfunction "TOG_7") (pintype "power_in"))
      (node (ref "DA23") (pin "10") (pinfunction "VSS_10") (pintype "power_in"))
      (node (ref "DA23") (pin "12") (pinfunction "SM_12") (pintype "power_in"))
      (node (ref "DA23") (pin "5") (pinfunction "AHLB_5") (pintype "power_in"))
      (node (ref "DA23") (pin "7") (pinfunction "TOG_7") (pintype "power_in"))
      (node (ref "DA24") (pin "10") (pinfunction "VSS_10") (pintype "power_in"))
      (node (ref "DA24") (pin "12") (pinfunction "SM_12") (pintype "power_in"))
      (node (ref "DA24") (pin "5") (pinfunction "AHLB_5") (pintype "power_in"))
      (node (ref "DA24") (pin "7") (pinfunction "TOG_7") (pintype "power_in"))
      (node (ref "DA25") (pin "10") (pinfunction "VSS_10") (pintype "power_in"))
      (node (ref "DA25") (pin "12") (pinfunction "SM_12") (pintype "power_in"))
      (node (ref "DA25") (pin "5") (pinfunction "AHLB_5") (pintype "power_in"))
      (node (ref "DA25") (pin "7") (pinfunction "TOG_7") (pintype "power_in"))
    )
    (net (code "27") (name "unconnected-(DA20-TP1-Pad2)") (class "Default")
      (node (ref "DA20") (pin "2") (pinfunction "TP1_2") (pintype "power_in"))
    )
    (net (code "28") (name "unconnected-(DA20-TP2-Pad3)") (class "Default")
      (node (ref "DA20") (pin "3") (pinfunction "TP2_3") (pintype "power_in"))
    )
    (net (code "29") (name "unconnected-(DA20-TPQ1-Pad15)") (class "Default")
      (node (ref "DA20") (pin "15") (pinfunction "TPQ1_15") (pintype "power_in"))
    )
    (net (code "30") (name "unconnected-(DA20-TPQ2-Pad14)") (class "Default")
      (node (ref "DA20") (pin "14") (pinfunction "TPQ2_14") (pintype "power_in"))
    )
    (net (code "31") (name "unconnected-(DA21-TP1-Pad2)") (class "Default")
      (node (ref "DA21") (pin "2") (pinfunction "TP1_2") (pintype "power_in"))
    )
    (net (code "32") (name "unconnected-(DA21-TP2-Pad3)") (class "Default")
      (node (ref "DA21") (pin "3") (pinfunction "TP2_3") (pintype "power_in"))
    )
    (net (code "33") (name "unconnected-(DA21-TPQ1-Pad15)") (class "Default")
      (node (ref "DA21") (pin "15") (pinfunction "TPQ1_15") (pintype "power_in"))
    )
    (net (code "34") (name "unconnected-(DA21-TPQ2-Pad14)") (class "Default")
      (node (ref "DA21") (pin "14") (pinfunction "TPQ2_14") (pintype "power_in"))
    )
    (net (code "35") (name "unconnected-(DA22-TP1-Pad2)") (class "Default")
      (node (ref "DA22") (pin "2") (pinfunction "TP1_2") (pintype "power_in"))
    )
    (net (code "36") (name "unconnected-(DA22-TP2-Pad3)") (class "Default")
      (node (ref "DA22") (pin "3") (pinfunction "TP2_3") (pintype "power_in"))
    )
    (net (code "37") (name "unconnected-(DA22-TPQ1-Pad15)") (class "Default")
      (node (ref "DA22") (pin "15") (pinfunction "TPQ1_15") (pintype "power_in"))
    )
    (net (code "38") (name "unconnected-(DA22-TPQ2-Pad14)") (class "Default")
      (node (ref "DA22") (pin "14") (pinfunction "TPQ2_14") (pintype "power_in"))
    )
    (net (code "39") (name "unconnected-(DA23-TP1-Pad2)") (class "Default")
      (node (ref "DA23") (pin "2") (pinfunction "TP1_2") (pintype "power_in"))
    )
    (net (code "40") (name "unconnected-(DA23-TP2-Pad3)") (class "Default")
      (node (ref "DA23") (pin "3") (pinfunction "TP2_3") (pintype "power_in"))
    )
    (net (code "41") (name "unconnected-(DA23-TPQ1-Pad15)") (class "Default")
      (node (ref "DA23") (pin "15") (pinfunction "TPQ1_15") (pintype "power_in"))
    )
    (net (code "42") (name "unconnected-(DA23-TPQ2-Pad14)") (class "Default")
      (node (ref "DA23") (pin "14") (pinfunction "TPQ2_14") (pintype "power_in"))
    )
    (net (code "43") (name "unconnected-(DA24-TP1-Pad2)") (class "Default")
      (node (ref "DA24") (pin "2") (pinfunction "TP1_2") (pintype "power_in"))
    )
    (net (code "44") (name "unconnected-(DA24-TP2-Pad3)") (class "Default")
      (node (ref "DA24") (pin "3") (pinfunction "TP2_3") (pintype "power_in"))
    )
    (net (code "45") (name "unconnected-(DA24-TPQ1-Pad15)") (class "Default")
      (node (ref "DA24") (pin "15") (pinfunction "TPQ1_15") (pintype "power_in"))
    )
    (net (code "46") (name "unconnected-(DA24-TPQ2-Pad14)") (class "Default")
      (node (ref "DA24") (pin "14") (pinfunction "TPQ2_14") (pintype "power_in"))
    )
    (net (code "47") (name "unconnected-(DA25-TP1-Pad2)") (class "Default")
      (node (ref "DA25") (pin "2") (pinfunction "TP1_2") (pintype "power_in"))
    )
    (net (code "48") (name "unconnected-(DA25-TP2-Pad3)") (class "Default")
      (node (ref "DA25") (pin "3") (pinfunction "TP2_3") (pintype "power_in"))
    )
    (net (code "49") (name "unconnected-(DA25-TPQ1-Pad15)") (class "Default")
      (node (ref "DA25") (pin "15") (pinfunction "TPQ1_15") (pintype "power_in"))
    )
    (net (code "50") (name "unconnected-(DA25-TPQ2-Pad14)") (class "Default")
      (node (ref "DA25") (pin "14") (pinfunction "TPQ2_14") (pintype "power_in"))
    )
  )
)
